# Motor_Controller_old.net
KiCad netlist of a schematic drawn in Altium Designer
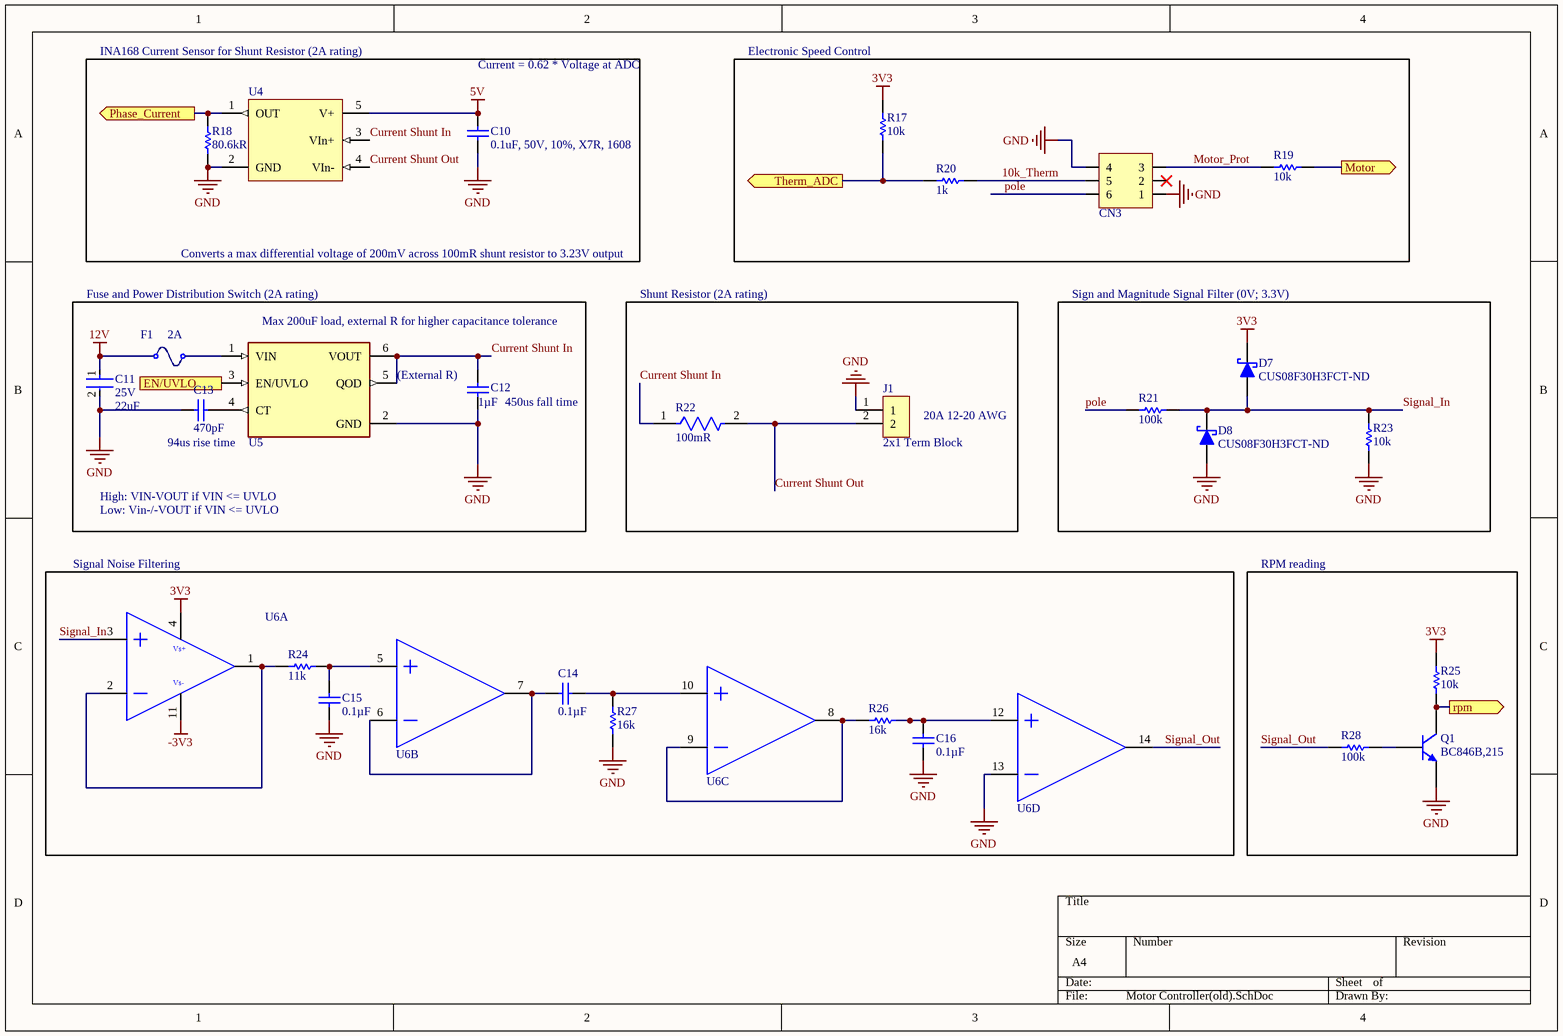
[diagram p0: Motor Controller(old).SchDoc]

(export (version "E")
  (design (tool "Eeschema 10.0.6"))
  (components
    (comp (ref "C10")
      (value "0.1uF, 50V, 10%, X7R, 1608")
      (footprint "CAPC1608N(0603\")")
      (description "CAP CER 0.1UF 50V 10% X7R 1608 (0603)")
      (fields
        (field (name "MANUFACTURER") "Samsung Electro-Mechanics America, Inc")
        (field (name "TOLERANCE") "±10%")
      )
      (libsource (lib "AUVIC") (part "Symbol"))
    )
    (comp (ref "C11")
      (value "GRM32ER71E226ME15K")
      (footprint "FP-GRM32-IPC_A")
      (description "CAP CER 22UF 25V X7R 1210")
      (fields
        (field (name "VOLTAGE") "25V")
        (field (name "CAPACITANCE") "22uF")
        (field (name "TOLERANCE") "20%")
      )
      (libsource (lib "AUVIC") (part "b4654b650e69147ec39a6b967a45e02"))
    )
    (comp (ref "C12")
      (value "1µF")
      (footprint "CAPC1608N(0603\")")
      (description "Capacitor, Ceramic, 50V, +/- 10%, 0603 SMD, X5R")
      (fields (field (name "Comment") "1uF 50V 0603 SMD, Ceramic") (field (name "CREATED BY") "Lyden Smith"))
      (libsource (lib "AUVIC") (part "Symbol"))
    )
    (comp (ref "C13")
      (value "470pF")
      (footprint "CAPC1608N(0603\")")
      (description "Capacitor, Ceramic, 50V, +/- 10%, 0603 SMD, X7R")
      (fields
        (field (name "Comment") "470pF 50V 0603 SMD, Ceramic")
        (field (name "PUBLISHER") "TRAXX Automation Ltd.")
      )
      (libsource (lib "") (part "Symbol_1"))
    )
    (comp (ref "C14")
      (value "0.1uF, 50V, 10%, X7R, 1608")
      (footprint "CAPC1608N(0603\")")
      (description "CAP CER 0.1UF 50V 10% X7R 1608 (0603)")
      (fields
        (field (name "MANUFACTURER") "Samsung Electro-Mechanics America, Inc")
        (field (name "MANUFACTURER PART NUMBER") "CL10B104KB8SFNC")
        (field (name "CAPACITANCE") "0.1µF")
      )
      (libsource (lib "AUVic_Integrated_Library_Capacitors") (part "0.1uF, 50V, 10%, X7R, 1608"))
    )
    (comp (ref "C15")
      (value "0.1uF, 50V, 10%, X7R, 1608")
      (footprint "CAPC1608N(0603\")")
      (description "CAP CER 0.1UF 50V 10% X7R 1608 (0603)")
      (fields
        (field (name "MANUFACTURER") "Samsung Electro-Mechanics America, Inc")
        (field (name "MANUFACTURER PART NUMBER") "CL10B104KB8SFNC")
        (field (name "CAPACITANCE") "0.1µF")
      )
      (libsource (lib "AUVic_Integrated_Library_Capacitors") (part "0.1uF, 50V, 10%, X7R, 1608"))
    )
    (comp (ref "C16")
      (value "0.1uF, 50V, 10%, X7R, 1608")
      (footprint "CAPC1608N(0603\")")
      (description "CAP CER 0.1UF 50V 10% X7R 1608 (0603)")
      (fields
        (field (name "MANUFACTURER") "Samsung Electro-Mechanics America, Inc")
        (field (name "MANUFACTURER PART NUMBER") "CL10B104KB8SFNC")
        (field (name "CAPACITANCE") "0.1µF")
      )
      (libsource (lib "AUVic_Integrated_Library_Capacitors") (part "0.1uF, 50V, 10%, X7R, 1608"))
    )
    (comp (ref "CN3")
      (value "Header, Male, 2x3 Conn, Shrouded, THT, 2MM RT ANG TIN")
      (footprint "HEADER, MALE, Shrouded, 6POS, 2MM, RT ANG,THT")
      (description "Header, Male, 2x3, Pitch: 0.1\" (2.54mm), THT")
      (fields
        (field (name "REVIEWED BY") "*")
        (field (name "PUBLISHER") "AUVic")
        (field (name "CREATED BY") "Andy Bates")
      )
      (libsource (lib "") (part "Symbol_3"))
    )
    (comp (ref "D7")
      (value "CUS08F30H3FCT-ND")
      (footprint "SC-76")
      (description "Diode, Schottky, 30V, 800mA")
      (fields
        (field (name "SUPPLIER PART NUMBER 1") "CUS08F30H3FCT-ND")
        (field (name "CREATED BY") "Andy Bates")
        (field (name "PUBLISHER") "AUVic")
      )
      (libsource (lib "AUVic_Integrated_Library_Diodes") (part "CUS08F30H3FCT-ND"))
    )
    (comp (ref "D8")
      (value "CUS08F30H3FCT-ND")
      (footprint "SC-76")
      (description "Diode, Schottky, 30V, 800mA")
      (fields
        (field (name "SUPPLIER PART NUMBER 1") "CUS08F30H3FCT-ND")
        (field (name "CREATED BY") "Andy Bates")
        (field (name "PUBLISHER") "AUVic")
      )
      (libsource (lib "AUVic_Integrated_Library_Diodes") (part "CUS08F30H3FCT-ND"))
    )
    (comp (ref "F1")
      (value "SMD Fuse, 2A, 63VAC, Slow Blow")
      (footprint "RESC1206(3216)")
      (description "Fuse, Smd, 2A, Slow Blow, 1206")
      (fields (field (name "CURRENT RATING") "2A"))
      (libsource (lib "") (part "Symbol_2"))
    )
    (comp (ref "J1")
      (value "2x1 Term Block")
      (footprint "2X1 Terminal Blocks Phoenix Contact 5mm")
      (fields (field (name "MADE BY") "Andy Bates"))
      (libsource (lib "AUVic_Integrated_Library_Connectors") (part "2x1 Terminal Block, 20A, 12-20AWG"))
    )
    (comp (ref "Q1")
      (value "BC846B,215")
      (footprint "SOT-23")
      (description "NPN 65V 100mA 250mW")
      (fields (field (name "PUBLISHER") "Andy Bates"))
      (libsource (lib "AUVic_Integrated_Library_Transistors") (part "BC846B,215"))
    )
    (comp (ref "R17")
      (value "10k")
      (footprint "RESC1608N(0603\")")
      (description "10kR, 1%, 1/10W, 0603 SMD")
      (fields (field (name "MADE BY") "Ashwin Sira"))
      (libsource (lib "AUVic_Integrated_Library_Resistors") (part "10kR, 1%, 1/10W, 0603 SMD"))
    )
    (comp (ref "R18")
      (value "80.6kR, 1%, 1/10W, 0603")
      (footprint "RESC0603(1608)_M")
      (description "Res Thick Film 0603 80.6K Ohm 1% 0.1W(1/10W) ±100ppm/C Molded SMD Automotive Paper T/R")
      (fields (field (name "TOLERANCE") "1%") (field (name "RESISTANCE") "80.6kR"))
      (libsource (lib "AUVIC") (part "RES"))
    )
    (comp (ref "R19")
      (value "10k")
      (footprint "RESC1608N(0603\")")
      (description "10kR, 1%, 1/10W, 0603 SMD")
      (fields (field (name "MADE BY") "Ashwin Sira"))
      (libsource (lib "AUVic_Integrated_Library_Resistors") (part "10kR, 1%, 1/10W, 0603 SMD"))
    )
    (comp (ref "R20")
      (value "1k")
      (footprint "RESC1608N(0603\")")
      (description "1kR, 1%, 1/10W , 0603, SMD")
      (fields (field (name "CREATED BY") "Andy Bates") (field (name "PUBLISHER") "AUVic"))
      (libsource (lib "AUVic_Integrated_Library_Resistors") (part "1kR, 1%, 1/10W , 0603, SMD"))
    )
    (comp (ref "R21")
      (value "100k")
      (footprint "RESC1608N(0603\")")
      (description "100kR, 1%, 1/10W, 0603 SMD")
      (fields (field (name "MADE BY") "Andy Bates"))
      (libsource (lib "AUVic_Integrated_Library_Resistors") (part "100kR, 1%, 1/10W, 0603 SMD"))
    )
    (comp (ref "R22")
      (value "RL2512FK-070R1L")
      (footprint "FP-RL2512-MFG")
      (description "Res Thick Film 2512 0.1 Ohm 1% 1W 600ppm/ C Molded SMD Embossed T/R")
      (fields (field (name "RESISTANCE") "100mR") (field (name "TOLERANCE") "5%"))
      (libsource (lib "AUVIC") (part "1029c3af85768c4190bb7ad29bc67b5"))
    )
    (comp (ref "R23")
      (value "10k")
      (footprint "RESC1608N(0603\")")
      (description "10kR, 1%, 1/10W, 0603 SMD")
      (fields (field (name "MADE BY") "Ashwin Sira"))
      (libsource (lib "AUVic_Integrated_Library_Resistors") (part "10kR, 1%, 1/10W, 0603 SMD"))
    )
    (comp (ref "R24")
      (value "11k")
      (footprint "RESC1608N(0603\")")
      (description "11kR, 1%, 1/10W, 0603 SMD")
      (fields (field (name "MADE BY") "Ashwin Sira"))
      (libsource (lib "AUVic_Integrated_Library_Resistors") (part "11kR, 1%, 1/10W, 0603 SMD"))
    )
    (comp (ref "R25")
      (value "10k")
      (footprint "RESC1608N(0603\")")
      (description "10kR, 1%, 1/10W, 0603 SMD")
      (fields (field (name "MADE BY") "Ashwin Sira"))
      (libsource (lib "AUVic_Integrated_Library_Resistors") (part "10kR, 1%, 1/10W, 0603 SMD"))
    )
    (comp (ref "R26")
      (value "16k")
      (footprint "RESC1608N(0603\")")
      (description "16kR, 1%, 1/10W, 0603 SMD")
      (fields (field (name "MADE BY") "Ashwin Sira"))
      (libsource (lib "AUVic_Integrated_Library_Resistors") (part "16kR, 1%, 1/10W, 0603 SMD"))
    )
    (comp (ref "R27")
      (value "16k")
      (footprint "RESC1608N(0603\")")
      (description "16kR, 1%, 1/10W, 0603 SMD")
      (fields (field (name "MADE BY") "Ashwin Sira"))
      (libsource (lib "AUVic_Integrated_Library_Resistors") (part "16kR, 1%, 1/10W, 0603 SMD"))
    )
    (comp (ref "R28")
      (value "100k")
      (footprint "RESC1608N(0603\")")
      (description "100kR, 1%, 1/10W, 0603 SMD")
      (fields (field (name "MADE BY") "Andy Bates"))
      (libsource (lib "AUVic_Integrated_Library_Resistors") (part "100kR, 1%, 1/10W, 0603 SMD"))
    )
    (comp (ref "U4")
      (value "INA168, Current Sensor, High-Side, Analog")
      (footprint "SOT23-5")
      (fields (field (name "CREATED BY") "Jacob Lower") (field (name "PUBLISHER") "AUVic"))
      (libsource (lib "AUVIC") (part "INA168, Current Sensor, High-Side, Analog"))
    )
    (comp (ref "U5")
      (value "TPS22810DBVT")
      (footprint "FP-DBV0006A-IPC_B")
      (description "TEXAS INSTRUMENTS - TPS22810DBVT - POWER LOAD SWITCH, 18V, SOT-23-6")
      (libsource (lib "AUVIC") (part "ee6d432fc15fefb7feee3c6afcaabb4"))
    )
    (comp (ref "U6")
      (value "Quad Op Amp TSV324")
      (footprint "SOP-14")
      (description "TSV324")
      (fields (field (name "PUBLISHER") "Altium Limited") (field (name "CREATED BY") "Jordan"))
      (libsource (lib "AUVic_Schematic_Library_Op_amps") (part "Quad Op Amp TSV324"))
    )
  )
  (nets
    (net (code "1") (name "-3V3") (class "Default")
      (node (ref "U6") (pin "11") (pinfunction "Vcc-_11") (pintype "passive"))
    )
    (net (code "2") (name "/10k_Therm") (class "Default")
      (node (ref "CN3") (pin "5") (pinfunction "5_5") (pintype "passive"))
      (node (ref "R20") (pin "2") (pinfunction "2_2") (pintype "passive"))
    )
    (net (code "3") (name "/Current Shunt In") (class "Default")
      (node (ref "C12") (pin "2") (pinfunction "Cathode_2") (pintype "passive"))
      (node (ref "R22") (pin "1") (pinfunction "1_1") (pintype "passive"))
      (node (ref "U4") (pin "3") (pinfunction "VIn+_3") (pintype "input"))
      (node (ref "U5") (pin "5") (pinfunction "QOD_5") (pintype "output"))
      (node (ref "U5") (pin "6") (pinfunction "VOUT_6") (pintype "power_in"))
    )
    (net (code "4") (name "/Current Shunt Out") (class "Default")
      (node (ref "J1") (pin "2") (pinfunction "2_2") (pintype "passive"))
      (node (ref "R22") (pin "2") (pinfunction "2_2") (pintype "passive"))
      (node (ref "U4") (pin "4") (pinfunction "VIn-_4") (pintype "input"))
    )
    (net (code "5") (name "/EN{slash}UVLO") (class "Default")
      (node (ref "U5") (pin "3") (pinfunction "EN/UVLO_3") (pintype "input"))
    )
    (net (code "6") (name "/Motor") (class "Default")
      (node (ref "R19") (pin "1") (pinfunction "1_1") (pintype "passive"))
    )
    (net (code "7") (name "/Motor_Prot") (class "Default")
      (node (ref "CN3") (pin "3") (pinfunction "3_3") (pintype "passive"))
      (node (ref "R19") (pin "2") (pinfunction "2_2") (pintype "passive"))
    )
    (net (code "8") (name "/Phase_Current") (class "Default")
      (node (ref "R18") (pin "2") (pinfunction "2_2") (pintype "passive"))
      (node (ref "U4") (pin "1") (pinfunction "OUT_1") (pintype "output"))
    )
    (net (code "9") (name "/Signal_In") (class "Default")
      (node (ref "D7") (pin "A") (pinfunction "Anode_A") (pintype "passive"))
      (node (ref "D8") (pin "K") (pinfunction "Cathode_K") (pintype "passive"))
      (node (ref "R21") (pin "1") (pinfunction "1_1") (pintype "passive"))
      (node (ref "R23") (pin "2") (pinfunction "2_2") (pintype "passive"))
      (node (ref "U6") (pin "3") (pinfunction "Non-Inverting_Input_1_3") (pintype "passive"))
    )
    (net (code "10") (name "/Signal_Out") (class "Default")
      (node (ref "R28") (pin "1") (pinfunction "1_1") (pintype "passive"))
      (node (ref "U6") (pin "14") (pinfunction "Output_4_14") (pintype "passive"))
    )
    (net (code "11") (name "/Therm_ADC") (class "Default")
      (node (ref "R17") (pin "1") (pinfunction "1_1") (pintype "passive"))
      (node (ref "R20") (pin "1") (pinfunction "1_1") (pintype "passive"))
    )
    (net (code "12") (name "/pole") (class "Default")
      (node (ref "CN3") (pin "6") (pinfunction "6_6") (pintype "passive"))
      (node (ref "R21") (pin "2") (pinfunction "2_2") (pintype "passive"))
    )
    (net (code "13") (name "/rpm") (class "Default")
      (node (ref "Q1") (pin "3") (pinfunction "C_3") (pintype "passive"))
      (node (ref "R25") (pin "1") (pinfunction "1_1") (pintype "passive"))
    )
    (net (code "14") (name "3V3") (class "Default")
      (node (ref "D7") (pin "K") (pinfunction "Cathode_K") (pintype "passive"))
      (node (ref "R17") (pin "2") (pinfunction "2_2") (pintype "passive"))
      (node (ref "R25") (pin "2") (pinfunction "2_2") (pintype "passive"))
      (node (ref "U6") (pin "4") (pinfunction "Vcc+_4") (pintype "passive"))
    )
    (net (code "15") (name "5V") (class "Default")
      (node (ref "C10") (pin "2") (pinfunction "Cathode_2") (pintype "passive"))
      (node (ref "U4") (pin "5") (pinfunction "V+_5") (pintype "power_in"))
    )
    (net (code "16") (name "12V") (class "Default")
      (node (ref "C11") (pin "1") (pinfunction "1_1") (pintype "passive"))
      (node (ref "F1") (pin "1") (pinfunction "1_1") (pintype "passive"))
    )
    (net (code "17") (name "GND") (class "Default")
      (node (ref "C10") (pin "1") (pinfunction "Anode_1") (pintype "passive"))
      (node (ref "C11") (pin "2") (pinfunction "2_2") (pintype "passive"))
      (node (ref "C12") (pin "1") (pinfunction "Anode_1") (pintype "passive"))
      (node (ref "C13") (pin "1") (pinfunction "1_1") (pintype "passive"))
      (node (ref "C15") (pin "1") (pinfunction "Anode_1") (pintype "passive"))
      (node (ref "C16") (pin "1") (pinfunction "Anode_1") (pintype "passive"))
      (node (ref "CN3") (pin "1") (pinfunction "1_1") (pintype "passive"))
      (node (ref "CN3") (pin "4") (pinfunction "4_4") (pintype "passive"))
      (node (ref "D8") (pin "A") (pinfunction "Anode_A") (pintype "passive"))
      (node (ref "J1") (pin "1") (pinfunction "1_1") (pintype "passive"))
      (node (ref "Q1") (pin "2") (pinfunction "E_2") (pintype "passive"))
      (node (ref "R18") (pin "1") (pinfunction "1_1") (pintype "passive"))
      (node (ref "R23") (pin "1") (pinfunction "1_1") (pintype "passive"))
      (node (ref "R27") (pin "1") (pinfunction "1_1") (pintype "passive"))
      (node (ref "U4") (pin "2") (pinfunction "GND_2") (pintype "power_in"))
      (node (ref "U5") (pin "2") (pinfunction "GND_2") (pintype "power_in"))
      (node (ref "U6") (pin "13") (pinfunction "Inverting_Input_3_13") (pintype "passive"))
    )
    (net (code "18") (name "Net-(C14-Anode)") (class "Default")
      (node (ref "C14") (pin "1") (pinfunction "Anode_1") (pintype "passive"))
      (node (ref "U6") (pin "6") (pinfunction "Inverting_Input_2_6") (pintype "passive"))
      (node (ref "U6") (pin "7") (pinfunction "Output_2_7") (pintype "passive"))
    )
    (net (code "19") (name "Net-(C14-Cathode)") (class "Default")
      (node (ref "C14") (pin "2") (pinfunction "Cathode_2") (pintype "passive"))
      (node (ref "R27") (pin "2") (pinfunction "2_2") (pintype "passive"))
      (node (ref "U6") (pin "10") (pinfunction "Non-Inverting_Input_3_10") (pintype "passive"))
    )
    (net (code "20") (name "Net-(C15-Cathode)") (class "Default")
      (node (ref "C15") (pin "2") (pinfunction "Cathode_2") (pintype "passive"))
      (node (ref "R24") (pin "2") (pinfunction "2_2") (pintype "passive"))
      (node (ref "U6") (pin "5") (pinfunction "Non-Inverting_Input_2_5") (pintype "passive"))
    )
    (net (code "21") (name "Net-(C16-Cathode)") (class "Default")
      (node (ref "C16") (pin "2") (pinfunction "Cathode_2") (pintype "passive"))
      (node (ref "R26") (pin "1") (pinfunction "1_1") (pintype "passive"))
      (node (ref "U6") (pin "12") (pinfunction "Non-Inverting_Input_4_12") (pintype "passive"))
    )
    (net (code "22") (name "Net-(Q1-B)") (class "Default")
      (node (ref "Q1") (pin "1") (pinfunction "B_1") (pintype "passive"))
      (node (ref "R28") (pin "2") (pinfunction "2_2") (pintype "passive"))
    )
    (net (code "23") (name "Net-(U5-CT)") (class "Default")
      (node (ref "C13") (pin "2") (pinfunction "2_2") (pintype "passive"))
      (node (ref "U5") (pin "4") (pinfunction "CT_4") (pintype "output"))
    )
    (net (code "24") (name "Net-(U5-VIN)") (class "Default")
      (node (ref "F1") (pin "2") (pinfunction "2_2") (pintype "passive"))
      (node (ref "U5") (pin "1") (pinfunction "VIN_1") (pintype "input"))
    )
    (net (code "25") (name "Net-(U6A-Inverting_Input_1)") (class "Default")
      (node (ref "R24") (pin "1") (pinfunction "1_1") (pintype "passive"))
      (node (ref "U6") (pin "1") (pinfunction "Output_1_1") (pintype "passive"))
      (node (ref "U6") (pin "2") (pinfunction "Inverting_Input_1_2") (pintype "passive"))
    )
    (net (code "26") (name "Net-(U6C-Inverting_Input_3)") (class "Default")
      (node (ref "R26") (pin "2") (pinfunction "2_2") (pintype "passive"))
      (node (ref "U6") (pin "8") (pinfunction "Output_3_8") (pintype "passive"))
      (node (ref "U6") (pin "9") (pinfunction "Inverting_Input_3_9") (pintype "passive"))
    )
    (net (code "27") (name "unconnected-(CN3-Pad2)") (class "Default")
      (node (ref "CN3") (pin "2") (pinfunction "2_2") (pintype "passive+no_connect"))
    )
  )
)
